# Power.net
KiCad netlist of a schematic drawn in Altium Designer
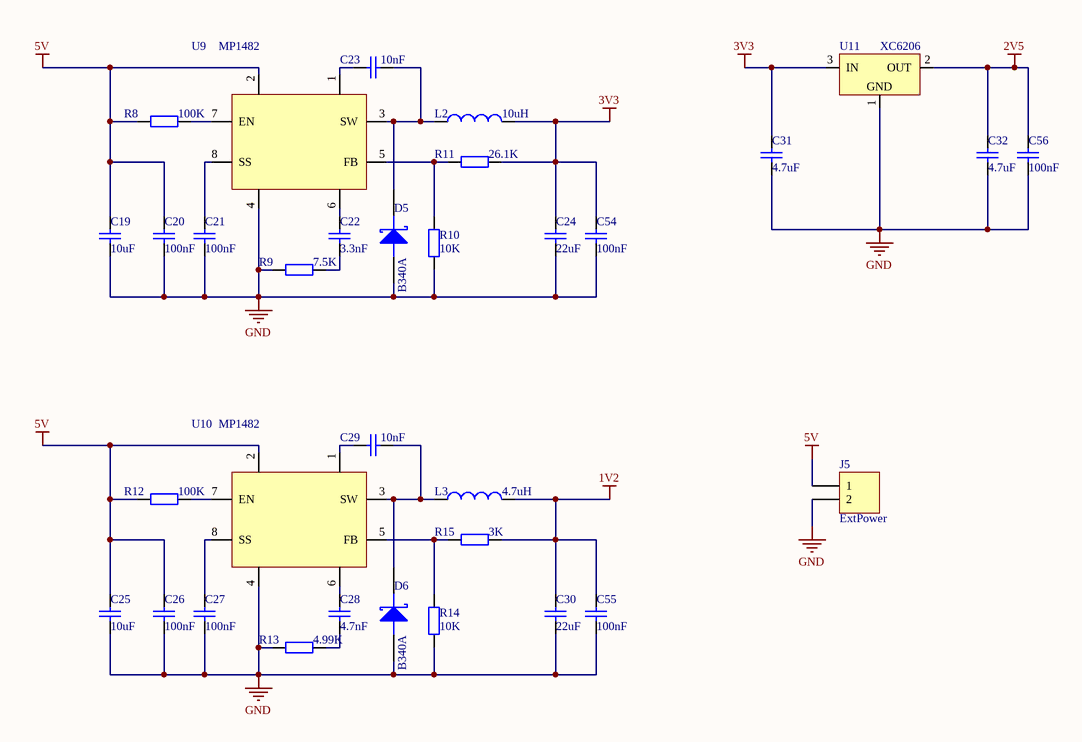
[diagram p0: Power.SchDoc]

(export (version "E")
  (design (tool "Eeschema 10.0.6"))
  (components
    (comp (ref "C19")
      (value "10uF")
      (footprint "C1206")
      (description "Capacitor")
      (fields (field (name "PUBLISHER") "Altium Limited"))
      (libsource (lib "Miscellaneous Devices") (part "Cap"))
    )
    (comp (ref "C20")
      (value "100nF")
      (footprint "C0603")
      (description "Capacitor")
      (fields (field (name "PUBLISHER") "Altium Limited"))
      (libsource (lib "Miscellaneous Devices") (part "Cap"))
    )
    (comp (ref "C21")
      (value "100nF")
      (footprint "C0603")
      (description "Capacitor")
      (fields (field (name "PUBLISHER") "Altium Limited"))
      (libsource (lib "Miscellaneous Devices") (part "Cap"))
    )
    (comp (ref "C22")
      (value "3.3nF")
      (footprint "C0603")
      (description "Capacitor")
      (fields (field (name "PUBLISHER") "Altium Limited"))
      (libsource (lib "Miscellaneous Devices") (part "Cap"))
    )
    (comp (ref "C23")
      (value "10nF")
      (footprint "C0603")
      (description "Capacitor")
      (fields (field (name "PUBLISHER") "Altium Limited"))
      (libsource (lib "Miscellaneous Devices") (part "Cap"))
    )
    (comp (ref "C24")
      (value "22uF")
      (footprint "C1206")
      (description "Capacitor")
      (fields (field (name "PUBLISHER") "Altium Limited"))
      (libsource (lib "Miscellaneous Devices") (part "Cap"))
    )
    (comp (ref "C25")
      (value "10uF")
      (footprint "C1206")
      (description "Capacitor")
      (fields (field (name "PUBLISHER") "Altium Limited"))
      (libsource (lib "Miscellaneous Devices") (part "Cap"))
    )
    (comp (ref "C26")
      (value "100nF")
      (footprint "C0603")
      (description "Capacitor")
      (fields (field (name "PUBLISHER") "Altium Limited"))
      (libsource (lib "Miscellaneous Devices") (part "Cap"))
    )
    (comp (ref "C27")
      (value "100nF")
      (footprint "C0603")
      (description "Capacitor")
      (fields (field (name "PUBLISHER") "Altium Limited"))
      (libsource (lib "Miscellaneous Devices") (part "Cap"))
    )
    (comp (ref "C28")
      (value "4.7nF")
      (footprint "C0603")
      (description "Capacitor")
      (fields (field (name "PUBLISHER") "Altium Limited"))
      (libsource (lib "Miscellaneous Devices") (part "Cap"))
    )
    (comp (ref "C29")
      (value "10nF")
      (footprint "C0603")
      (description "Capacitor")
      (fields (field (name "PUBLISHER") "Altium Limited"))
      (libsource (lib "Miscellaneous Devices") (part "Cap"))
    )
    (comp (ref "C30")
      (value "22uF")
      (footprint "C1206")
      (description "Capacitor")
      (fields (field (name "PUBLISHER") "Altium Limited"))
      (libsource (lib "Miscellaneous Devices") (part "Cap"))
    )
    (comp (ref "C31")
      (value "4.7uF")
      (footprint "C0603")
      (description "Capacitor")
      (fields (field (name "PUBLISHER") "Altium Limited"))
      (libsource (lib "Miscellaneous Devices") (part "Cap"))
    )
    (comp (ref "C32")
      (value "4.7uF")
      (footprint "C0603")
      (description "Capacitor")
      (fields (field (name "PUBLISHER") "Altium Limited"))
      (libsource (lib "Miscellaneous Devices") (part "Cap"))
    )
    (comp (ref "C54")
      (value "100nF")
      (footprint "C0603")
      (description "Capacitor")
      (fields (field (name "PUBLISHER") "Altium Limited"))
      (libsource (lib "Miscellaneous Devices") (part "Cap"))
    )
    (comp (ref "C55")
      (value "100nF")
      (footprint "C0603")
      (description "Capacitor")
      (fields (field (name "PUBLISHER") "Altium Limited"))
      (libsource (lib "Miscellaneous Devices") (part "Cap"))
    )
    (comp (ref "C56")
      (value "100nF")
      (footprint "C0603")
      (description "Capacitor")
      (fields (field (name "PUBLISHER") "Altium Limited"))
      (libsource (lib "Miscellaneous Devices") (part "Cap"))
    )
    (comp (ref "D5")
      (value "B340A")
      (footprint "SMA")
      (description "Schottky Diode")
      (libsource (lib "JL_SCH") (part "DIODE SCHOTTKY"))
    )
    (comp (ref "D6")
      (value "B340A")
      (footprint "SMA")
      (description "Schottky Diode")
      (libsource (lib "JL_SCH") (part "DIODE SCHOTTKY"))
    )
    (comp (ref "J5")
      (value "ExtPower")
      (footprint "HDR1X2")
      (description "Header, 2-Pin")
      (fields (field (name "PUBLISHER") "Altium Limited"))
      (libsource (lib "Common Headers") (part "Header 2"))
    )
    (comp (ref "L2")
      (value "10uH")
      (footprint "CDRH5D28")
      (description "Inductor")
      (fields (field (name "PUBLISHER") "Altium Limited"))
      (libsource (lib "Miscellaneous Devices") (part "Inductor"))
    )
    (comp (ref "L3")
      (value "4.7uH")
      (footprint "CDRH5D28")
      (description "Inductor")
      (fields (field (name "PUBLISHER") "Altium Limited"))
      (libsource (lib "Miscellaneous Devices") (part "Inductor"))
    )
    (comp (ref "R8")
      (value "100K")
      (footprint "R0603")
      (description "Resistor")
      (fields (field (name "PUBLISHER") "Altium Limited"))
      (libsource (lib "Miscellaneous Devices") (part "Res2"))
    )
    (comp (ref "R9")
      (value "7.5K")
      (footprint "R0603")
      (description "Resistor")
      (fields (field (name "PUBLISHER") "Altium Limited"))
      (libsource (lib "Miscellaneous Devices") (part "Res2"))
    )
    (comp (ref "R10")
      (value "10K")
      (footprint "R0603")
      (description "Resistor")
      (fields (field (name "PUBLISHER") "Altium Limited"))
      (libsource (lib "") (part "Res2_1"))
    )
    (comp (ref "R11")
      (value "26.1K")
      (footprint "R0603")
      (description "Resistor")
      (fields (field (name "PUBLISHER") "Altium Limited"))
      (libsource (lib "Miscellaneous Devices") (part "Res2"))
    )
    (comp (ref "R12")
      (value "100K")
      (footprint "R0603")
      (description "Resistor")
      (fields (field (name "PUBLISHER") "Altium Limited"))
      (libsource (lib "Miscellaneous Devices") (part "Res2"))
    )
    (comp (ref "R13")
      (value "4.99K")
      (footprint "R0603")
      (description "Resistor")
      (fields (field (name "PUBLISHER") "Altium Limited"))
      (libsource (lib "Miscellaneous Devices") (part "Res2"))
    )
    (comp (ref "R14")
      (value "10K")
      (footprint "R0603")
      (description "Resistor")
      (fields (field (name "PUBLISHER") "Altium Limited"))
      (libsource (lib "") (part "Res2_1"))
    )
    (comp (ref "R15")
      (value "3K")
      (footprint "R0603")
      (description "Resistor")
      (fields (field (name "PUBLISHER") "Altium Limited"))
      (libsource (lib "Miscellaneous Devices") (part "Res2"))
    )
    (comp (ref "U9") (value "MP1482") (footprint "SOIC-8") (libsource (lib "ssmaster_1") (part "MP1482")))
    (comp (ref "U10") (value "MP1482") (footprint "SOIC-8") (libsource (lib "ssmaster_1") (part "MP1482")))
    (comp (ref "U11")
      (value "XC6206")
      (footprint "sot-23-xc6206")
      (description "LDO")
      (libsource (lib "ssmaster_1") (part "XC6206"))
    )
  )
  (nets
    (net (code "1") (name "1V2") (class "Default")
      (node (ref "C30") (pin "1") (pinfunction "1_1") (pintype "passive"))
      (node (ref "C55") (pin "2") (pinfunction "2_2") (pintype "passive"))
      (node (ref "L3") (pin "2") (pinfunction "2_2") (pintype "passive"))
      (node (ref "R15") (pin "1") (pinfunction "1_1") (pintype "passive"))
    )
    (net (code "2") (name "2V5") (class "Default")
      (node (ref "C32") (pin "2") (pinfunction "2_2") (pintype "passive"))
      (node (ref "C56") (pin "2") (pinfunction "2_2") (pintype "passive"))
      (node (ref "U11") (pin "2") (pinfunction "OUT_2") (pintype "power_in"))
    )
    (net (code "3") (name "3V3") (class "Default")
      (node (ref "C24") (pin "1") (pinfunction "1_1") (pintype "passive"))
      (node (ref "C31") (pin "2") (pinfunction "2_2") (pintype "passive"))
      (node (ref "C54") (pin "2") (pinfunction "2_2") (pintype "passive"))
      (node (ref "L2") (pin "2") (pinfunction "2_2") (pintype "passive"))
      (node (ref "R11") (pin "1") (pinfunction "1_1") (pintype "passive"))
      (node (ref "U11") (pin "3") (pinfunction "IN_3") (pintype "power_in"))
    )
    (net (code "4") (name "5V") (class "Default")
      (node (ref "C19") (pin "2") (pinfunction "2_2") (pintype "passive"))
      (node (ref "C20") (pin "2") (pinfunction "2_2") (pintype "passive"))
      (node (ref "C25") (pin "2") (pinfunction "2_2") (pintype "passive"))
      (node (ref "C26") (pin "2") (pinfunction "2_2") (pintype "passive"))
      (node (ref "J5") (pin "1") (pinfunction "1_1") (pintype "passive"))
      (node (ref "R12") (pin "2") (pinfunction "2_2") (pintype "passive"))
      (node (ref "R8") (pin "2") (pinfunction "2_2") (pintype "passive"))
      (node (ref "U10") (pin "2") (pinfunction "IN_2") (pintype "power_in"))
      (node (ref "U9") (pin "2") (pinfunction "IN_2") (pintype "power_in"))
    )
    (net (code "5") (name "GND") (class "Default")
      (node (ref "C19") (pin "1") (pinfunction "1_1") (pintype "passive"))
      (node (ref "C20") (pin "1") (pinfunction "1_1") (pintype "passive"))
      (node (ref "C21") (pin "1") (pinfunction "1_1") (pintype "passive"))
      (node (ref "C24") (pin "2") (pinfunction "2_2") (pintype "passive"))
      (node (ref "C25") (pin "1") (pinfunction "1_1") (pintype "passive"))
      (node (ref "C26") (pin "1") (pinfunction "1_1") (pintype "passive"))
      (node (ref "C27") (pin "1") (pinfunction "1_1") (pintype "passive"))
      (node (ref "C30") (pin "2") (pinfunction "2_2") (pintype "passive"))
      (node (ref "C31") (pin "1") (pinfunction "1_1") (pintype "passive"))
      (node (ref "C32") (pin "1") (pinfunction "1_1") (pintype "passive"))
      (node (ref "C54") (pin "1") (pinfunction "1_1") (pintype "passive"))
      (node (ref "C55") (pin "1") (pinfunction "1_1") (pintype "passive"))
      (node (ref "C56") (pin "1") (pinfunction "1_1") (pintype "passive"))
      (node (ref "D5") (pin "1") (pinfunction "A_1") (pintype "passive"))
      (node (ref "D6") (pin "1") (pinfunction "A_1") (pintype "passive"))
      (node (ref "J5") (pin "2") (pinfunction "2_2") (pintype "passive"))
      (node (ref "R10") (pin "1") (pinfunction "1_1") (pintype "passive"))
      (node (ref "R13") (pin "2") (pinfunction "2_2") (pintype "passive"))
      (node (ref "R14") (pin "1") (pinfunction "1_1") (pintype "passive"))
      (node (ref "R9") (pin "2") (pinfunction "2_2") (pintype "passive"))
      (node (ref "U10") (pin "4") (pinfunction "GND_4") (pintype "power_in"))
      (node (ref "U11") (pin "1") (pinfunction "GND_1") (pintype "power_in"))
      (node (ref "U9") (pin "4") (pinfunction "GND_4") (pintype "power_in"))
    )
    (net (code "6") (name "Net-(C22-Pad1)") (class "Default")
      (node (ref "C22") (pin "1") (pinfunction "1_1") (pintype "passive"))
      (node (ref "R9") (pin "1") (pinfunction "1_1") (pintype "passive"))
    )
    (net (code "7") (name "Net-(C28-Pad1)") (class "Default")
      (node (ref "C28") (pin "1") (pinfunction "1_1") (pintype "passive"))
      (node (ref "R13") (pin "1") (pinfunction "1_1") (pintype "passive"))
    )
    (net (code "8") (name "Net-(D5-K)") (class "Default")
      (node (ref "C23") (pin "1") (pinfunction "1_1") (pintype "passive"))
      (node (ref "D5") (pin "2") (pinfunction "K_2") (pintype "passive"))
      (node (ref "L2") (pin "1") (pinfunction "1_1") (pintype "passive"))
      (node (ref "U9") (pin "3") (pinfunction "SW_3") (pintype "passive"))
    )
    (net (code "9") (name "Net-(D6-K)") (class "Default")
      (node (ref "C29") (pin "1") (pinfunction "1_1") (pintype "passive"))
      (node (ref "D6") (pin "2") (pinfunction "K_2") (pintype "passive"))
      (node (ref "L3") (pin "1") (pinfunction "1_1") (pintype "passive"))
      (node (ref "U10") (pin "3") (pinfunction "SW_3") (pintype "passive"))
    )
    (net (code "10") (name "Net-(U9-BS)") (class "Default")
      (node (ref "C23") (pin "2") (pinfunction "2_2") (pintype "passive"))
      (node (ref "U9") (pin "1") (pinfunction "BS_1") (pintype "passive"))
    )
    (net (code "11") (name "Net-(U9-COMP)") (class "Default")
      (node (ref "C22") (pin "2") (pinfunction "2_2") (pintype "passive"))
      (node (ref "U9") (pin "6") (pinfunction "COMP_6") (pintype "passive"))
    )
    (net (code "12") (name "Net-(U9-EN)") (class "Default")
      (node (ref "R8") (pin "1") (pinfunction "1_1") (pintype "passive"))
      (node (ref "U9") (pin "7") (pinfunction "EN_7") (pintype "passive"))
    )
    (net (code "13") (name "Net-(U9-FB)") (class "Default")
      (node (ref "R10") (pin "2") (pinfunction "2_2") (pintype "passive"))
      (node (ref "R11") (pin "2") (pinfunction "2_2") (pintype "passive"))
      (node (ref "U9") (pin "5") (pinfunction "FB_5") (pintype "passive"))
    )
    (net (code "14") (name "Net-(U9-SS)") (class "Default")
      (node (ref "C21") (pin "2") (pinfunction "2_2") (pintype "passive"))
      (node (ref "U9") (pin "8") (pinfunction "SS_8") (pintype "passive"))
    )
    (net (code "15") (name "Net-(U10-BS)") (class "Default")
      (node (ref "C29") (pin "2") (pinfunction "2_2") (pintype "passive"))
      (node (ref "U10") (pin "1") (pinfunction "BS_1") (pintype "passive"))
    )
    (net (code "16") (name "Net-(U10-COMP)") (class "Default")
      (node (ref "C28") (pin "2") (pinfunction "2_2") (pintype "passive"))
      (node (ref "U10") (pin "6") (pinfunction "COMP_6") (pintype "passive"))
    )
    (net (code "17") (name "Net-(U10-EN)") (class "Default")
      (node (ref "R12") (pin "1") (pinfunction "1_1") (pintype "passive"))
      (node (ref "U10") (pin "7") (pinfunction "EN_7") (pintype "passive"))
    )
    (net (code "18") (name "Net-(U10-FB)") (class "Default")
      (node (ref "R14") (pin "2") (pinfunction "2_2") (pintype "passive"))
      (node (ref "R15") (pin "2") (pinfunction "2_2") (pintype "passive"))
      (node (ref "U10") (pin "5") (pinfunction "FB_5") (pintype "passive"))
    )
    (net (code "19") (name "Net-(U10-SS)") (class "Default")
      (node (ref "C27") (pin "2") (pinfunction "2_2") (pintype "passive"))
      (node (ref "U10") (pin "8") (pinfunction "SS_8") (pintype "passive"))
    )
  )
)
